# M8-TempAlarm.net
KiCad netlist of a schematic drawn in EAGLE
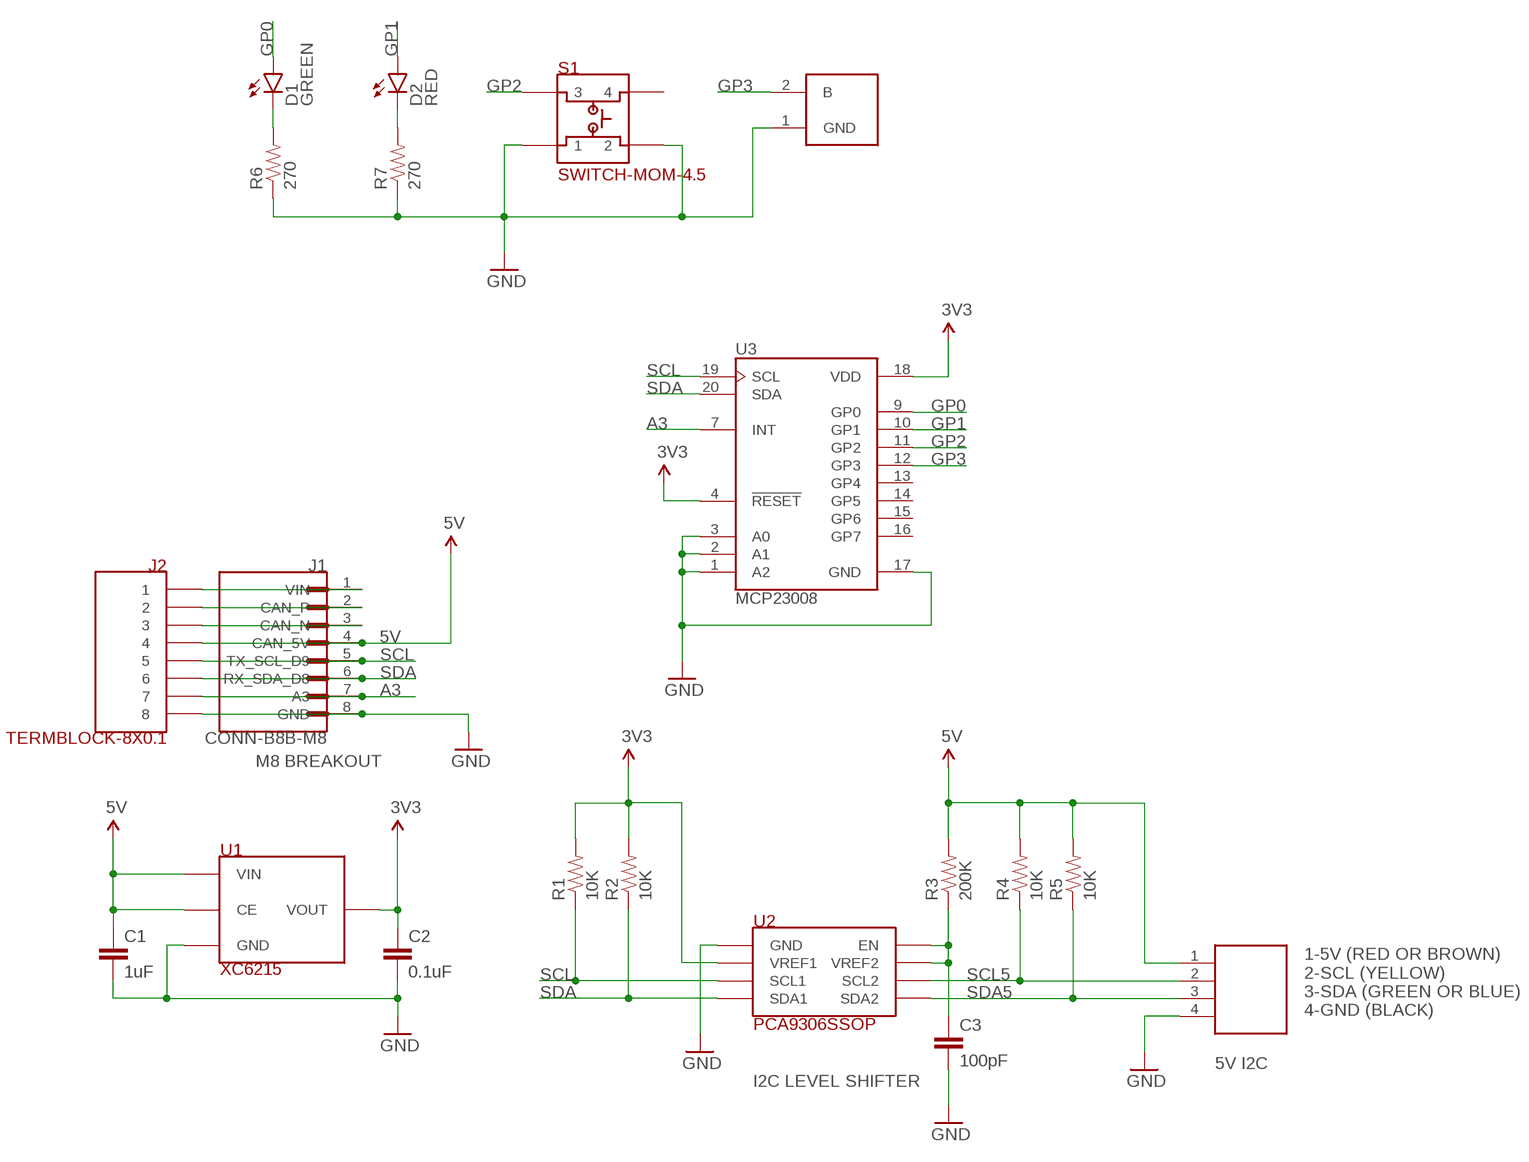
[diagram p0: schematic, sheet 1]

(export (version "E")
  (design (tool "Eeschema 10.0.6"))
  (components
    (comp (ref "C1")
      (value "1uF")
      (footprint "eagle-import:0603-CAP")
      (libsource (lib "eagle-import") (part "CAP-1UF-0603.DEV"))
    )
    (comp (ref "C2")
      (value "0.1uF")
      (footprint "eagle-import:0603-CAP")
      (libsource (lib "eagle-import") (part "CAP-0.1UF-0603"))
    )
    (comp (ref "C3")
      (value "100pF")
      (footprint "eagle-import:0603-CAP")
      (libsource (lib "eagle-import") (part "CAP-100PF-0603"))
    )
    (comp (ref "D1")
      (value "GREEN")
      (footprint "eagle-import:LED-0603")
      (libsource (lib "eagle-import") (part "LED-GREEN0603"))
    )
    (comp (ref "D2")
      (value "RED")
      (footprint "eagle-import:LED-0603")
      (libsource (lib "eagle-import") (part "LED-RED"))
    )
    (comp (ref "J1")
      (value "CONN-B8B-M8")
      (footprint "eagle-import:JST_B8B-PH-SM4-TB(LF)(SN)")
      (libsource (lib "eagle-import") (part "CONN-B8B-M8"))
    )
    (comp (ref "J2")
      (value "TERMBLOCK-8X0.1")
      (footprint "eagle-import:TERMBLOCK-8X0.1")
      (libsource (lib "eagle-import") (part "TERMBLOCK-8X0.1"))
    )
    (comp (ref "R1")
      (value "10K")
      (footprint "eagle-import:0603-RES")
      (libsource (lib "eagle-import") (part "RES-10K-06030603"))
    )
    (comp (ref "R2")
      (value "10K")
      (footprint "eagle-import:0603-RES")
      (libsource (lib "eagle-import") (part "RES-10K-06030603"))
    )
    (comp (ref "R3")
      (value "200K")
      (footprint "eagle-import:0603-RES")
      (libsource (lib "eagle-import") (part "RES-200K-0603"))
    )
    (comp (ref "R4")
      (value "10K")
      (footprint "eagle-import:0603-RES")
      (libsource (lib "eagle-import") (part "RES-10K-06030603"))
    )
    (comp (ref "R5")
      (value "10K")
      (footprint "eagle-import:0603-RES")
      (libsource (lib "eagle-import") (part "RES-10K-06030603"))
    )
    (comp (ref "R6")
      (value "270")
      (footprint "eagle-import:0603-RES")
      (libsource (lib "eagle-import") (part "RES-270-0603.DEV"))
    )
    (comp (ref "R7")
      (value "270")
      (footprint "eagle-import:0603-RES")
      (libsource (lib "eagle-import") (part "RES-270-0603.DEV"))
    )
    (comp (ref "S1")
      (value "SWITCH-MOM-4.5")
      (footprint "eagle-import:SWITCH-MOM-4.5")
      (libsource (lib "eagle-import") (part "SWITCH-MOM-4.5"))
    )
    (comp (ref "U$1")
      (value "TERMBLOCK-4X0.15")
      (footprint "eagle-import:TERMBLOCK-4X0.15")
      (libsource (lib "eagle-import") (part "TERMBLOCK-4X0.15"))
    )
    (comp (ref "U$2")
      (value "BUZZER2")
      (footprint "eagle-import:BUZZER2")
      (libsource (lib "eagle-import") (part "BUZZER2"))
    )
    (comp (ref "U1")
      (value "XC6215")
      (footprint "eagle-import:SOT-25-TOREX")
      (libsource (lib "eagle-import") (part "XC6215"))
    )
    (comp (ref "U2")
      (value "PCA9306SSOP")
      (footprint "eagle-import:8-SSOP-TI")
      (libsource (lib "eagle-import") (part "PCA9306SSOP"))
    )
    (comp (ref "U3")
      (value "MCP23008")
      (footprint "eagle-import:QFN21P50_400X400X100L40X24T270N")
      (fields (field (name "MF") "Microchip Technology") (field (name "MP") "MCP23008T-E/ML"))
      (libsource (lib "eagle-import") (part "MCP23008T-E/ML"))
    )
  )
  (nets
    (net (code "1") (name "/A3") (class "Default")
      (node (ref "J1") (pin "7") (pinfunction "A3_7") (pintype "passive"))
      (node (ref "J2") (pin "P$7") (pinfunction "7_P$7") (pintype "passive"))
      (node (ref "U3") (pin "7") (pinfunction "INT_7") (pintype "output"))
    )
    (net (code "2") (name "/GP0") (class "Default")
      (node (ref "D1") (pin "A") (pinfunction "A_A") (pintype "passive"))
      (node (ref "U3") (pin "9") (pinfunction "GP0_9") (pintype "bidirectional"))
    )
    (net (code "3") (name "/GP1") (class "Default")
      (node (ref "D2") (pin "A") (pinfunction "A_A") (pintype "passive"))
      (node (ref "U3") (pin "10") (pinfunction "GP1_10") (pintype "bidirectional"))
    )
    (net (code "4") (name "/GP2") (class "Default")
      (node (ref "S1") (pin "3") (pinfunction "3_3") (pintype "passive"))
      (node (ref "U3") (pin "11") (pinfunction "GP2_11") (pintype "bidirectional"))
    )
    (net (code "5") (name "/GP3") (class "Default")
      (node (ref "U$2") (pin "2") (pinfunction "B_2") (pintype "input"))
      (node (ref "U3") (pin "12") (pinfunction "GP3_12") (pintype "bidirectional"))
    )
    (net (code "6") (name "/SCL") (class "Default")
      (node (ref "J1") (pin "5") (pinfunction "TX_SCL_D9_5") (pintype "passive"))
      (node (ref "J2") (pin "P$5") (pinfunction "5_P$5") (pintype "passive"))
      (node (ref "R1") (pin "1") (pinfunction "1_1") (pintype "passive"))
      (node (ref "U2") (pin "3") (pinfunction "SCL1_3") (pintype "bidirectional"))
      (node (ref "U3") (pin "19") (pinfunction "SCL_19") (pintype "input"))
    )
    (net (code "7") (name "/SCL5") (class "Default")
      (node (ref "R4") (pin "1") (pinfunction "1_1") (pintype "passive"))
      (node (ref "U$1") (pin "2") (pinfunction "2_2") (pintype "passive"))
      (node (ref "U2") (pin "6") (pinfunction "SCL2_6") (pintype "bidirectional"))
    )
    (net (code "8") (name "/SDA") (class "Default")
      (node (ref "J1") (pin "6") (pinfunction "RX_SDA_D8_6") (pintype "passive"))
      (node (ref "J2") (pin "P$6") (pinfunction "6_P$6") (pintype "passive"))
      (node (ref "R2") (pin "1") (pinfunction "1_1") (pintype "passive"))
      (node (ref "U2") (pin "4") (pinfunction "SDA1_4") (pintype "bidirectional"))
      (node (ref "U3") (pin "20") (pinfunction "SDA_20") (pintype "bidirectional"))
    )
    (net (code "9") (name "/SDA5") (class "Default")
      (node (ref "R5") (pin "1") (pinfunction "1_1") (pintype "passive"))
      (node (ref "U$1") (pin "3") (pinfunction "3_3") (pintype "passive"))
      (node (ref "U2") (pin "5") (pinfunction "SDA2_5") (pintype "bidirectional"))
    )
    (net (code "10") (name "3V3") (class "Default")
      (node (ref "C2") (pin "1") (pinfunction "1_1") (pintype "passive"))
      (node (ref "R1") (pin "2") (pinfunction "2_2") (pintype "passive"))
      (node (ref "R2") (pin "2") (pinfunction "2_2") (pintype "passive"))
      (node (ref "U1") (pin "5") (pinfunction "VOUT_5") (pintype "passive"))
      (node (ref "U2") (pin "2") (pinfunction "VREF1_2") (pintype "power_in"))
      (node (ref "U3") (pin "18") (pinfunction "VDD_18") (pintype "power_in"))
      (node (ref "U3") (pin "4") (pinfunction "~{RESET}_4") (pintype "input"))
    )
    (net (code "11") (name "5V") (class "Default")
      (node (ref "C1") (pin "1") (pinfunction "1_1") (pintype "passive"))
      (node (ref "J1") (pin "4") (pinfunction "CAN_5V_4") (pintype "passive"))
      (node (ref "J2") (pin "P$4") (pinfunction "4_P$4") (pintype "passive"))
      (node (ref "R3") (pin "2") (pinfunction "2_2") (pintype "passive"))
      (node (ref "R4") (pin "2") (pinfunction "2_2") (pintype "passive"))
      (node (ref "R5") (pin "2") (pinfunction "2_2") (pintype "passive"))
      (node (ref "U$1") (pin "1") (pinfunction "1_1") (pintype "passive"))
      (node (ref "U1") (pin "1") (pinfunction "VIN_1") (pintype "passive"))
      (node (ref "U1") (pin "3") (pinfunction "CE_3") (pintype "input"))
    )
    (net (code "12") (name "GND") (class "Default")
      (node (ref "C1") (pin "2") (pinfunction "2_2") (pintype "passive"))
      (node (ref "C2") (pin "2") (pinfunction "2_2") (pintype "passive"))
      (node (ref "C3") (pin "2") (pinfunction "2_2") (pintype "passive"))
      (node (ref "J1") (pin "8") (pinfunction "GND_8") (pintype "passive"))
      (node (ref "J2") (pin "P$8") (pinfunction "8_P$8") (pintype "passive"))
      (node (ref "R6") (pin "1") (pinfunction "1_1") (pintype "passive"))
      (node (ref "R7") (pin "1") (pinfunction "1_1") (pintype "passive"))
      (node (ref "S1") (pin "1") (pinfunction "1_1") (pintype "passive"))
      (node (ref "S1") (pin "2") (pinfunction "2_2") (pintype "passive"))
      (node (ref "U$1") (pin "4") (pinfunction "4_4") (pintype "passive"))
      (node (ref "U$2") (pin "1") (pinfunction "GND_1") (pintype "passive"))
      (node (ref "U1") (pin "2") (pinfunction "GND_2") (pintype "passive"))
      (node (ref "U2") (pin "1") (pinfunction "GND_1") (pintype "passive"))
      (node (ref "U3") (pin "1") (pinfunction "A2_1") (pintype "bidirectional"))
      (node (ref "U3") (pin "17") (pinfunction "GND_17") (pintype "power_in"))
      (node (ref "U3") (pin "2") (pinfunction "A1_2") (pintype "input"))
      (node (ref "U3") (pin "3") (pinfunction "A0_3") (pintype "input"))
    )
    (net (code "13") (name "Net-(D1-PadC)") (class "Default")
      (node (ref "D1") (pin "C") (pinfunction "C_C") (pintype "passive"))
      (node (ref "R6") (pin "2") (pinfunction "2_2") (pintype "passive"))
    )
    (net (code "14") (name "Net-(D2-PadC)") (class "Default")
      (node (ref "D2") (pin "C") (pinfunction "C_C") (pintype "passive"))
      (node (ref "R7") (pin "2") (pinfunction "2_2") (pintype "passive"))
    )
    (net (code "15") (name "Net-(J1-CAN_N)") (class "Default")
      (node (ref "J1") (pin "3") (pinfunction "CAN_N_3") (pintype "passive"))
      (node (ref "J2") (pin "P$3") (pinfunction "3_P$3") (pintype "passive"))
    )
    (net (code "16") (name "Net-(J1-CAN_P)") (class "Default")
      (node (ref "J1") (pin "2") (pinfunction "CAN_P_2") (pintype "passive"))
      (node (ref "J2") (pin "P$2") (pinfunction "2_P$2") (pintype "passive"))
    )
    (net (code "17") (name "Net-(J1-VIN)") (class "Default")
      (node (ref "J1") (pin "1") (pinfunction "VIN_1") (pintype "passive"))
      (node (ref "J2") (pin "P$1") (pinfunction "1_P$1") (pintype "passive"))
    )
    (net (code "18") (name "Net-(U2-EN)") (class "Default")
      (node (ref "C3") (pin "1") (pinfunction "1_1") (pintype "passive"))
      (node (ref "R3") (pin "1") (pinfunction "1_1") (pintype "passive"))
      (node (ref "U2") (pin "7") (pinfunction "VREF2_7") (pintype "input"))
      (node (ref "U2") (pin "8") (pinfunction "EN_8") (pintype "input"))
    )
    (net (code "19") (name "unconnected-(S1-Pad4)") (class "Default")
      (node (ref "S1") (pin "4") (pinfunction "4_4") (pintype "passive"))
    )
    (net (code "20") (name "unconnected-(U3-GP4-Pad13)") (class "Default")
      (node (ref "U3") (pin "13") (pinfunction "GP4_13") (pintype "bidirectional"))
    )
    (net (code "21") (name "unconnected-(U3-GP5-Pad14)") (class "Default")
      (node (ref "U3") (pin "14") (pinfunction "GP5_14") (pintype "bidirectional"))
    )
    (net (code "22") (name "unconnected-(U3-GP6-Pad15)") (class "Default")
      (node (ref "U3") (pin "15") (pinfunction "GP6_15") (pintype "bidirectional"))
    )
    (net (code "23") (name "unconnected-(U3-GP7-Pad16)") (class "Default")
      (node (ref "U3") (pin "16") (pinfunction "GP7_16") (pintype "bidirectional"))
    )
  )
)
